# 2_PWR_BUCK.net
KiCad netlist of a schematic drawn in Altium Designer
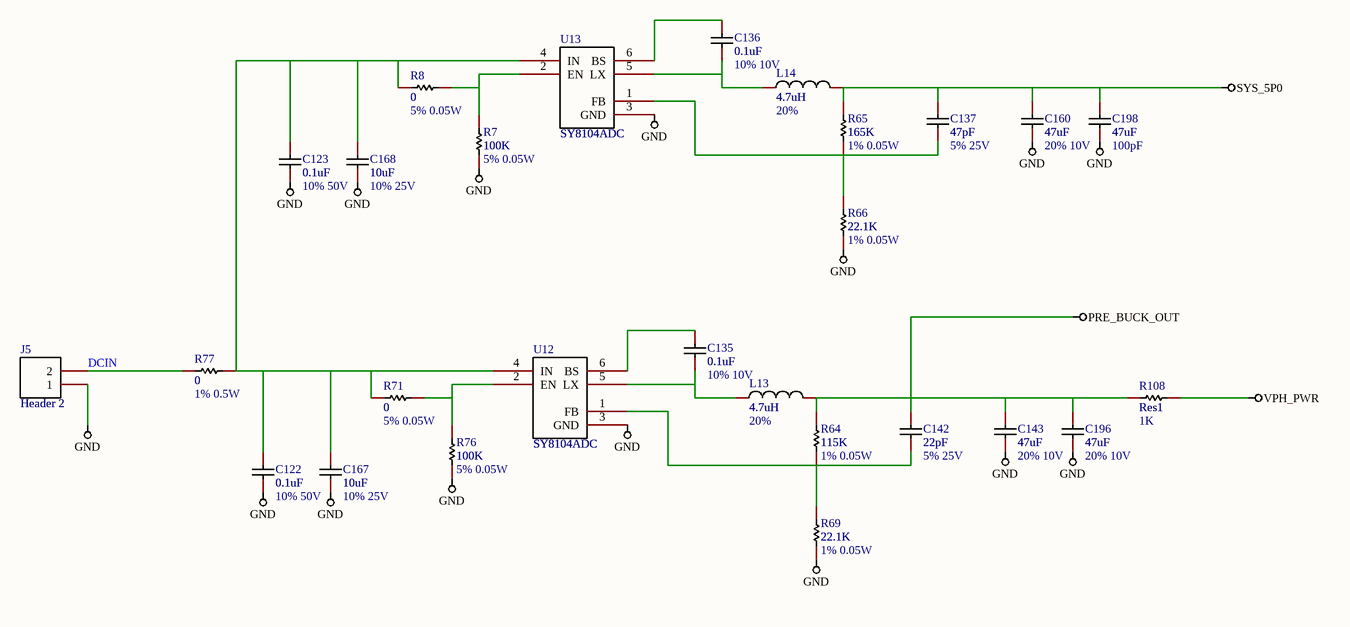
[diagram p0: 2_PWR_BUCK.schdoc]

(export (version "E")
  (design (tool "Eeschema 10.0.6"))
  (components
    (comp (ref "C122")
      (value "0.1uF")
      (description "Capacitor")
      (fields
        (field (name "NAME") "0.1uF")
        (field (name "ALTIUM_VALUE") "10% 50V")
        (field (name "PUBLISHER") "Altium Limited")
      )
      (libsource (lib "altium-import") (part "root_1_0.1uF_"))
    )
    (comp (ref "C123")
      (value "0.1uF")
      (description "Capacitor")
      (fields
        (field (name "NAME") "0.1uF")
        (field (name "ALTIUM_VALUE") "10% 50V")
        (field (name "PUBLISHER") "Altium Limited")
      )
      (libsource (lib "altium-import") (part "root_1_0.1uF_"))
    )
    (comp (ref "C135")
      (value "0.1uF")
      (description "Capacitor")
      (fields
        (field (name "NAME") "0.1uF")
        (field (name "ALTIUM_VALUE") "10% 10V")
        (field (name "PUBLISHER") "Altium Limited")
      )
      (libsource (lib "altium-import") (part "root_1_0.1uF_"))
    )
    (comp (ref "C136")
      (value "0.1uF")
      (description "Capacitor")
      (fields
        (field (name "NAME") "0.1uF")
        (field (name "ALTIUM_VALUE") "10% 10V")
        (field (name "PUBLISHER") "Altium Limited")
      )
      (libsource (lib "altium-import") (part "root_1_0.1uF_"))
    )
    (comp (ref "C137")
      (value "47pF")
      (description "Capacitor")
      (fields
        (field (name "NAME") "47pF")
        (field (name "ALTIUM_VALUE") "5% 25V")
        (field (name "PUBLISHER") "Altium Limited")
      )
      (libsource (lib "altium-import") (part "root_1_47pF_"))
    )
    (comp (ref "C142")
      (value "22pF")
      (description "Capacitor")
      (fields
        (field (name "NAME") "22pF")
        (field (name "ALTIUM_VALUE") "5% 25V")
        (field (name "PUBLISHER") "Altium Limited")
      )
      (libsource (lib "altium-import") (part "root_1_22pF_"))
    )
    (comp (ref "C143")
      (value "47uF")
      (description "Capacitor")
      (fields
        (field (name "NAME") "47uF")
        (field (name "ALTIUM_VALUE") "20% 10V")
        (field (name "PUBLISHER") "Altium Limited")
      )
      (libsource (lib "altium-import") (part "root_1_47uF_"))
    )
    (comp (ref "C160")
      (value "47uF")
      (description "Capacitor")
      (fields
        (field (name "NAME") "47uF")
        (field (name "ALTIUM_VALUE") "20% 10V")
        (field (name "PUBLISHER") "Altium Limited")
      )
      (libsource (lib "altium-import") (part "root_1_47uF_"))
    )
    (comp (ref "C167")
      (value "10uF")
      (description "Capacitor")
      (fields
        (field (name "NAME") "10uF")
        (field (name "ALTIUM_VALUE") "10% 25V")
        (field (name "PUBLISHER") "Altium Limited")
      )
      (libsource (lib "altium-import") (part "root_1_10uF_"))
    )
    (comp (ref "C168")
      (value "10uF")
      (description "Capacitor")
      (fields
        (field (name "NAME") "10uF")
        (field (name "ALTIUM_VALUE") "10% 25V")
        (field (name "PUBLISHER") "Altium Limited")
      )
      (libsource (lib "altium-import") (part "root_1_10uF_"))
    )
    (comp (ref "C196")
      (value "47uF")
      (description "Capacitor")
      (fields
        (field (name "NAME") "47uF")
        (field (name "ALTIUM_VALUE") "20% 10V")
        (field (name "PUBLISHER") "Altium Limited")
      )
      (libsource (lib "altium-import") (part "root_1_47uF_"))
    )
    (comp (ref "C198")
      (value "47uF")
      (description "Capacitor")
      (fields
        (field (name "NAME") "47uF")
        (field (name "ALTIUM_VALUE") "100pF")
        (field (name "PUBLISHER") "Altium Limited")
      )
      (libsource (lib "altium-import") (part "root_1_47uF_"))
    )
    (comp (ref "J5")
      (value "Header 2")
      (description "Header, 2-Pin")
      (fields (field (name "NAME") "Header 2") (field (name "PUBLISHER") "Altium Limited"))
      (libsource (lib "altium-import") (part "root_2_Header 2_"))
    )
    (comp (ref "L13")
      (value "4.7uH")
      (description "Inductor")
      (fields
        (field (name "NAME") "4.7uH")
        (field (name "ALTIUM_VALUE") "20%")
        (field (name "PUBLISHER") "Altium Limited")
      )
      (libsource (lib "altium-import") (part "root_0_4.7uH_"))
    )
    (comp (ref "L14")
      (value "4.7uH")
      (description "Inductor")
      (fields
        (field (name "NAME") "4.7uH")
        (field (name "ALTIUM_VALUE") "20%")
        (field (name "PUBLISHER") "Altium Limited")
      )
      (libsource (lib "altium-import") (part "root_0_4.7uH_"))
    )
    (comp (ref "R7")
      (value "100K")
      (description "Resistor")
      (fields
        (field (name "NAME") "100K")
        (field (name "ALTIUM_VALUE") "5% 0.05W")
        (field (name "PUBLISHER") "Altium Limited")
      )
      (libsource (lib "altium-import") (part "root_1_100K_"))
    )
    (comp (ref "R8")
      (value "0")
      (description "Resistor")
      (fields
        (field (name "NAME") "0")
        (field (name "ALTIUM_VALUE") "5% 0.05W")
        (field (name "PUBLISHER") "Altium Limited")
      )
      (libsource (lib "altium-import") (part "root_0_0_"))
    )
    (comp (ref "R64")
      (value "115K")
      (description "Resistor")
      (fields
        (field (name "NAME") "115K")
        (field (name "ALTIUM_VALUE") "1% 0.05W")
        (field (name "PUBLISHER") "Altium Limited")
      )
      (libsource (lib "altium-import") (part "root_1_115K_"))
    )
    (comp (ref "R65")
      (value "165K")
      (description "Resistor")
      (fields
        (field (name "NAME") "165K")
        (field (name "ALTIUM_VALUE") "1% 0.05W")
        (field (name "PUBLISHER") "Altium Limited")
      )
      (libsource (lib "altium-import") (part "root_1_165K_"))
    )
    (comp (ref "R66")
      (value "22.1K")
      (description "Resistor")
      (fields
        (field (name "NAME") "22.1K")
        (field (name "ALTIUM_VALUE") "1% 0.05W")
        (field (name "PUBLISHER") "Altium Limited")
      )
      (libsource (lib "altium-import") (part "root_1_22.1K_"))
    )
    (comp (ref "R69")
      (value "22.1K")
      (description "Resistor")
      (fields
        (field (name "NAME") "22.1K")
        (field (name "ALTIUM_VALUE") "1% 0.05W")
        (field (name "PUBLISHER") "Altium Limited")
      )
      (libsource (lib "altium-import") (part "root_1_22.1K_"))
    )
    (comp (ref "R71")
      (value "0")
      (description "Resistor")
      (fields
        (field (name "NAME") "0")
        (field (name "ALTIUM_VALUE") "5% 0.05W")
        (field (name "PUBLISHER") "Altium Limited")
      )
      (libsource (lib "altium-import") (part "root_0_0_"))
    )
    (comp (ref "R76")
      (value "100K")
      (description "Resistor")
      (fields
        (field (name "NAME") "100K")
        (field (name "ALTIUM_VALUE") "5% 0.05W")
        (field (name "PUBLISHER") "Altium Limited")
      )
      (libsource (lib "altium-import") (part "root_1_100K_"))
    )
    (comp (ref "R77")
      (value "0")
      (description "Resistor")
      (fields
        (field (name "NAME") "0")
        (field (name "ALTIUM_VALUE") "1% 0.5W")
        (field (name "PUBLISHER") "Altium Limited")
      )
      (libsource (lib "altium-import") (part "root_0_0_"))
    )
    (comp (ref "R108")
      (value "Res1")
      (description "Resistor")
      (fields
        (field (name "NAME") "Res1")
        (field (name "ALTIUM_VALUE") "1K")
        (field (name "PUBLISHER") "Altium Limited")
      )
      (libsource (lib "altium-import") (part "root_0_Res1_"))
    )
    (comp (ref "U12")
      (value "SY8104ADC")
      (fields (field (name "NAME") "SY8104ADC") (field (name "LIBRARY NAME") "MSM8916_DRAM_PMIC_REF_Library"))
      (libsource (lib "altium-import") (part "root_0_SY8104ADC_"))
    )
    (comp (ref "U13")
      (value "SY8104ADC")
      (fields (field (name "NAME") "SY8104ADC") (field (name "LIBRARY NAME") "MSM8916_DRAM_PMIC_REF_Library"))
      (libsource (lib "altium-import") (part "root_0_SY8104ADC_"))
    )
  )
  (nets
    (net (code "1") (name "/DCIN") (class "Default")
      (node (ref "J5") (pin "2") (pinfunction "2_2") (pintype "passive"))
      (node (ref "R77") (pin "1") (pinfunction "1_1") (pintype "passive"))
    )
    (net (code "2") (name "GND") (class "Default")
      (node (ref "C122") (pin "1") (pinfunction "1_1") (pintype "passive"))
      (node (ref "C123") (pin "1") (pinfunction "1_1") (pintype "passive"))
      (node (ref "C143") (pin "1") (pinfunction "1_1") (pintype "passive"))
      (node (ref "C160") (pin "1") (pinfunction "1_1") (pintype "passive"))
      (node (ref "C167") (pin "1") (pinfunction "1_1") (pintype "passive"))
      (node (ref "C168") (pin "1") (pinfunction "1_1") (pintype "passive"))
      (node (ref "C196") (pin "1") (pinfunction "1_1") (pintype "passive"))
      (node (ref "C198") (pin "1") (pinfunction "1_1") (pintype "passive"))
      (node (ref "J5") (pin "1") (pinfunction "1_1") (pintype "passive"))
      (node (ref "R66") (pin "1") (pinfunction "1_1") (pintype "passive"))
      (node (ref "R69") (pin "1") (pinfunction "1_1") (pintype "passive"))
      (node (ref "R7") (pin "1") (pinfunction "1_1") (pintype "passive"))
      (node (ref "R76") (pin "1") (pinfunction "1_1") (pintype "passive"))
      (node (ref "U12") (pin "3") (pinfunction "GND_3") (pintype "passive"))
      (node (ref "U13") (pin "3") (pinfunction "GND_3") (pintype "passive"))
    )
    (net (code "3") (name "Net-(U12-BS)") (class "Default")
      (node (ref "C135") (pin "2") (pinfunction "2_2") (pintype "passive"))
      (node (ref "U12") (pin "6") (pinfunction "BS_6") (pintype "passive"))
    )
    (net (code "4") (name "Net-(U12-EN)") (class "Default")
      (node (ref "R71") (pin "2") (pinfunction "2_2") (pintype "passive"))
      (node (ref "R76") (pin "2") (pinfunction "2_2") (pintype "passive"))
      (node (ref "U12") (pin "2") (pinfunction "EN_2") (pintype "passive"))
    )
    (net (code "5") (name "Net-(U12-FB)") (class "Default")
      (node (ref "C142") (pin "1") (pinfunction "1_1") (pintype "passive"))
      (node (ref "R64") (pin "1") (pinfunction "1_1") (pintype "passive"))
      (node (ref "R69") (pin "2") (pinfunction "2_2") (pintype "passive"))
      (node (ref "U12") (pin "1") (pinfunction "FB_1") (pintype "passive"))
    )
    (net (code "6") (name "Net-(U12-IN)") (class "Default")
      (node (ref "C122") (pin "2") (pinfunction "2_2") (pintype "passive"))
      (node (ref "C123") (pin "2") (pinfunction "2_2") (pintype "passive"))
      (node (ref "C167") (pin "2") (pinfunction "2_2") (pintype "passive"))
      (node (ref "C168") (pin "2") (pinfunction "2_2") (pintype "passive"))
      (node (ref "R71") (pin "1") (pinfunction "1_1") (pintype "passive"))
      (node (ref "R77") (pin "2") (pinfunction "2_2") (pintype "passive"))
      (node (ref "R8") (pin "1") (pinfunction "1_1") (pintype "passive"))
      (node (ref "U12") (pin "4") (pinfunction "IN_4") (pintype "passive"))
      (node (ref "U13") (pin "4") (pinfunction "IN_4") (pintype "passive"))
    )
    (net (code "7") (name "Net-(U12-LX)") (class "Default")
      (node (ref "C135") (pin "1") (pinfunction "1_1") (pintype "passive"))
      (node (ref "L13") (pin "1") (pinfunction "1_1") (pintype "passive"))
      (node (ref "U12") (pin "5") (pinfunction "LX_5") (pintype "passive"))
    )
    (net (code "8") (name "Net-(U13-BS)") (class "Default")
      (node (ref "C136") (pin "2") (pinfunction "2_2") (pintype "passive"))
      (node (ref "U13") (pin "6") (pinfunction "BS_6") (pintype "passive"))
    )
    (net (code "9") (name "Net-(U13-EN)") (class "Default")
      (node (ref "R7") (pin "2") (pinfunction "2_2") (pintype "passive"))
      (node (ref "R8") (pin "2") (pinfunction "2_2") (pintype "passive"))
      (node (ref "U13") (pin "2") (pinfunction "EN_2") (pintype "passive"))
    )
    (net (code "10") (name "Net-(U13-FB)") (class "Default")
      (node (ref "C137") (pin "1") (pinfunction "1_1") (pintype "passive"))
      (node (ref "R65") (pin "1") (pinfunction "1_1") (pintype "passive"))
      (node (ref "R66") (pin "2") (pinfunction "2_2") (pintype "passive"))
      (node (ref "U13") (pin "1") (pinfunction "FB_1") (pintype "passive"))
    )
    (net (code "11") (name "Net-(U13-LX)") (class "Default")
      (node (ref "C136") (pin "1") (pinfunction "1_1") (pintype "passive"))
      (node (ref "L14") (pin "1") (pinfunction "1_1") (pintype "passive"))
      (node (ref "U13") (pin "5") (pinfunction "LX_5") (pintype "passive"))
    )
    (net (code "12") (name "PRE_BUCK_OUT") (class "Default")
      (node (ref "C142") (pin "2") (pinfunction "2_2") (pintype "passive"))
      (node (ref "C143") (pin "2") (pinfunction "2_2") (pintype "passive"))
      (node (ref "C196") (pin "2") (pinfunction "2_2") (pintype "passive"))
      (node (ref "L13") (pin "2") (pinfunction "2_2") (pintype "passive"))
      (node (ref "R108") (pin "1") (pinfunction "1_1") (pintype "passive"))
      (node (ref "R64") (pin "2") (pinfunction "2_2") (pintype "passive"))
    )
    (net (code "13") (name "SYS_5P0") (class "Default")
      (node (ref "C137") (pin "2") (pinfunction "2_2") (pintype "passive"))
      (node (ref "C160") (pin "2") (pinfunction "2_2") (pintype "passive"))
      (node (ref "C198") (pin "2") (pinfunction "2_2") (pintype "passive"))
      (node (ref "L14") (pin "2") (pinfunction "2_2") (pintype "passive"))
      (node (ref "R65") (pin "2") (pinfunction "2_2") (pintype "passive"))
    )
    (net (code "14") (name "VPH_PWR") (class "Default")
      (node (ref "R108") (pin "2") (pinfunction "2_2") (pintype "passive"))
    )
  )
)
